# Breadproto.net
KiCad netlist of a schematic drawn in EAGLE
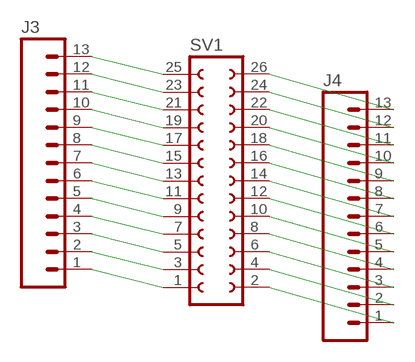
[diagram p0: schematic, sheet 1]

(export (version "E")
  (design (tool "Eeschema 10.0.6"))
  (components
    (comp (ref "J3")
      (value "M13")
      (footprint "eagle-import:1X13")
      (libsource (lib "eagle-import") (part "M13"))
    )
    (comp (ref "J4")
      (value "M13")
      (footprint "eagle-import:1X13")
      (libsource (lib "eagle-import") (part "M13"))
    )
    (comp (ref "SV1")
      (value "FE13-2")
      (footprint "eagle-import:FE13-2")
      (libsource (lib "eagle-import") (part "FE13-2"))
    )
  )
  (nets
    (net (code "1") (name "Net-(J3-Pad1)") (class "Default")
      (node (ref "J3") (pin "1") (pinfunction "1_1") (pintype "passive"))
      (node (ref "SV1") (pin "1") (pinfunction "1_1") (pintype "passive"))
    )
    (net (code "2") (name "Net-(J3-Pad2)") (class "Default")
      (node (ref "J3") (pin "2") (pinfunction "2_2") (pintype "passive"))
      (node (ref "SV1") (pin "3") (pinfunction "3_3") (pintype "passive"))
    )
    (net (code "3") (name "Net-(J3-Pad3)") (class "Default")
      (node (ref "J3") (pin "3") (pinfunction "3_3") (pintype "passive"))
      (node (ref "SV1") (pin "5") (pinfunction "5_5") (pintype "passive"))
    )
    (net (code "4") (name "Net-(J3-Pad4)") (class "Default")
      (node (ref "J3") (pin "4") (pinfunction "4_4") (pintype "passive"))
      (node (ref "SV1") (pin "7") (pinfunction "7_7") (pintype "passive"))
    )
    (net (code "5") (name "Net-(J3-Pad5)") (class "Default")
      (node (ref "J3") (pin "5") (pinfunction "5_5") (pintype "passive"))
      (node (ref "SV1") (pin "9") (pinfunction "9_9") (pintype "passive"))
    )
    (net (code "6") (name "Net-(J3-Pad6)") (class "Default")
      (node (ref "J3") (pin "6") (pinfunction "6_6") (pintype "passive"))
      (node (ref "SV1") (pin "11") (pinfunction "11_11") (pintype "passive"))
    )
    (net (code "7") (name "Net-(J3-Pad7)") (class "Default")
      (node (ref "J3") (pin "7") (pinfunction "7_7") (pintype "passive"))
      (node (ref "SV1") (pin "13") (pinfunction "13_13") (pintype "passive"))
    )
    (net (code "8") (name "Net-(J3-Pad8)") (class "Default")
      (node (ref "J3") (pin "8") (pinfunction "8_8") (pintype "passive"))
      (node (ref "SV1") (pin "15") (pinfunction "15_15") (pintype "passive"))
    )
    (net (code "9") (name "Net-(J3-Pad9)") (class "Default")
      (node (ref "J3") (pin "9") (pinfunction "9_9") (pintype "passive"))
      (node (ref "SV1") (pin "17") (pinfunction "17_17") (pintype "passive"))
    )
    (net (code "10") (name "Net-(J3-Pad10)") (class "Default")
      (node (ref "J3") (pin "10") (pinfunction "10_10") (pintype "passive"))
      (node (ref "SV1") (pin "19") (pinfunction "19_19") (pintype "passive"))
    )
    (net (code "11") (name "Net-(J3-Pad11)") (class "Default")
      (node (ref "J3") (pin "11") (pinfunction "11_11") (pintype "passive"))
      (node (ref "SV1") (pin "21") (pinfunction "21_21") (pintype "passive"))
    )
    (net (code "12") (name "Net-(J3-Pad12)") (class "Default")
      (node (ref "J3") (pin "12") (pinfunction "12_12") (pintype "passive"))
      (node (ref "SV1") (pin "23") (pinfunction "23_23") (pintype "passive"))
    )
    (net (code "13") (name "Net-(J3-Pad13)") (class "Default")
      (node (ref "J3") (pin "13") (pinfunction "13_13") (pintype "passive"))
      (node (ref "SV1") (pin "25") (pinfunction "25_25") (pintype "passive"))
    )
    (net (code "14") (name "Net-(J4-Pad1)") (class "Default")
      (node (ref "J4") (pin "1") (pinfunction "1_1") (pintype "passive"))
      (node (ref "SV1") (pin "2") (pinfunction "2_2") (pintype "passive"))
    )
    (net (code "15") (name "Net-(J4-Pad2)") (class "Default")
      (node (ref "J4") (pin "2") (pinfunction "2_2") (pintype "passive"))
      (node (ref "SV1") (pin "4") (pinfunction "4_4") (pintype "passive"))
    )
    (net (code "16") (name "Net-(J4-Pad3)") (class "Default")
      (node (ref "J4") (pin "3") (pinfunction "3_3") (pintype "passive"))
      (node (ref "SV1") (pin "6") (pinfunction "6_6") (pintype "passive"))
    )
    (net (code "17") (name "Net-(J4-Pad4)") (class "Default")
      (node (ref "J4") (pin "4") (pinfunction "4_4") (pintype "passive"))
      (node (ref "SV1") (pin "8") (pinfunction "8_8") (pintype "passive"))
    )
    (net (code "18") (name "Net-(J4-Pad5)") (class "Default")
      (node (ref "J4") (pin "5") (pinfunction "5_5") (pintype "passive"))
      (node (ref "SV1") (pin "10") (pinfunction "10_10") (pintype "passive"))
    )
    (net (code "19") (name "Net-(J4-Pad6)") (class "Default")
      (node (ref "J4") (pin "6") (pinfunction "6_6") (pintype "passive"))
      (node (ref "SV1") (pin "12") (pinfunction "12_12") (pintype "passive"))
    )
    (net (code "20") (name "Net-(J4-Pad7)") (class "Default")
      (node (ref "J4") (pin "7") (pinfunction "7_7") (pintype "passive"))
      (node (ref "SV1") (pin "14") (pinfunction "14_14") (pintype "passive"))
    )
    (net (code "21") (name "Net-(J4-Pad8)") (class "Default")
      (node (ref "J4") (pin "8") (pinfunction "8_8") (pintype "passive"))
      (node (ref "SV1") (pin "16") (pinfunction "16_16") (pintype "passive"))
    )
    (net (code "22") (name "Net-(J4-Pad9)") (class "Default")
      (node (ref "J4") (pin "9") (pinfunction "9_9") (pintype "passive"))
      (node (ref "SV1") (pin "18") (pinfunction "18_18") (pintype "passive"))
    )
    (net (code "23") (name "Net-(J4-Pad10)") (class "Default")
      (node (ref "J4") (pin "10") (pinfunction "10_10") (pintype "passive"))
      (node (ref "SV1") (pin "20") (pinfunction "20_20") (pintype "passive"))
    )
    (net (code "24") (name "Net-(J4-Pad11)") (class "Default")
      (node (ref "J4") (pin "11") (pinfunction "11_11") (pintype "passive"))
      (node (ref "SV1") (pin "22") (pinfunction "22_22") (pintype "passive"))
    )
    (net (code "25") (name "Net-(J4-Pad12)") (class "Default")
      (node (ref "J4") (pin "12") (pinfunction "12_12") (pintype "passive"))
      (node (ref "SV1") (pin "24") (pinfunction "24_24") (pintype "passive"))
    )
    (net (code "26") (name "Net-(J4-Pad13)") (class "Default")
      (node (ref "J4") (pin "13") (pinfunction "13_13") (pintype "passive"))
      (node (ref "SV1") (pin "26") (pinfunction "26_26") (pintype "passive"))
    )
  )
)
